# HRT.net
KiCad netlist of a schematic drawn in Altium Designer
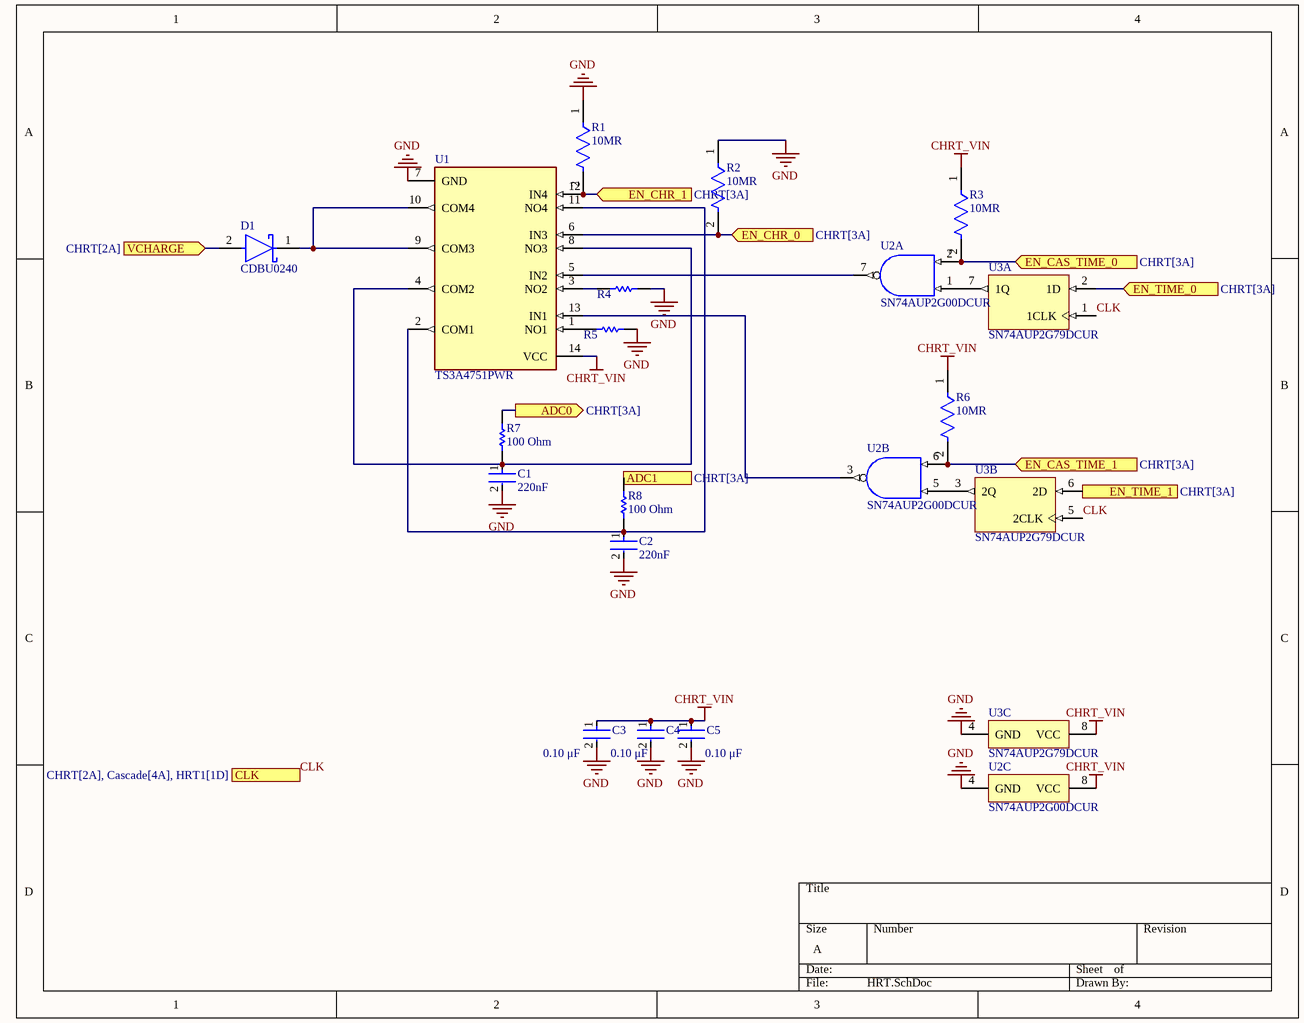
[diagram p0: HRT.SchDoc]

(export (version "E")
  (design (tool "Eeschema 10.0.6"))
  (components
    (comp (ref "C1")
      (value "GRM155R71C224KA12D")
      (footprint "FP-GRM155-0_05-IPC_C")
      (description "Chip Multilayer Ceramic Capacitors for General Purpose, 0402, 0.22uF, X7R, 15%, 10%, 16V")
      (fields
        (field (name "CAPACITANCE") "220nF")
        (field (name "VOLTAGE") "16V")
        (field (name "TOLERANCE") "10%")
      )
      (libsource (lib "Altium Content Vault") (part "02cd4be3c70576c341d710602a673aa"))
    )
    (comp (ref "C2")
      (value "GRM155R71C224KA12D")
      (footprint "FP-GRM155-0_05-IPC_C")
      (description "Chip Multilayer Ceramic Capacitors for General Purpose, 0402, 0.22uF, X7R, 15%, 10%, 16V")
      (fields
        (field (name "CAPACITANCE") "220nF")
        (field (name "VOLTAGE") "16V")
        (field (name "TOLERANCE") "10%")
      )
      (libsource (lib "Altium Content Vault") (part "02cd4be3c70576c341d710602a673aa"))
    )
    (comp (ref "C3")
      (value "C0402C104K8PACTU")
      (footprint "FP-C0402-BB-MFG")
      (description "CAP CER 0.1UF 10V X5R 0402")
      (fields
        (field (name "CAPACITANCE") "0.10 μF")
        (field (name "MANUFACTURER") "Kemet")
        (field (name "TOLERANCE") "0.1")
      )
      (libsource (lib "Altium Content Vault") (part "b4654b650e69147ec39a6b967a45e02"))
    )
    (comp (ref "C4")
      (value "C0402C104K8PACTU")
      (footprint "FP-C0402-BB-MFG")
      (description "CAP CER 0.1UF 10V X5R 0402")
      (fields
        (field (name "CAPACITANCE") "0.10 μF")
        (field (name "MANUFACTURER") "Kemet")
        (field (name "TOLERANCE") "0.1")
      )
      (libsource (lib "Altium Content Vault") (part "b4654b650e69147ec39a6b967a45e02"))
    )
    (comp (ref "C5")
      (value "C0402C104K8PACTU")
      (footprint "FP-C0402-BB-MFG")
      (description "CAP CER 0.1UF 10V X5R 0402")
      (fields
        (field (name "CAPACITANCE") "0.10 μF")
        (field (name "MANUFACTURER") "Kemet")
        (field (name "TOLERANCE") "0.1")
      )
      (libsource (lib "Altium Content Vault") (part "b4654b650e69147ec39a6b967a45e02"))
    )
    (comp (ref "D1")
      (value "CDBU0240")
      (footprint "FP-SOD-523F-MFG")
      (description "DIODE SCHOTTKY 40V 200MA 0603")
      (libsource (lib "Altium Content Vault") (part "1d6ec82d83fb6aee721767c19dac4b9"))
    )
    (comp (ref "R1")
      (value "CRCW040210M0JNED")
      (footprint "FP-CRCW0402-e3-IPC_C")
      (description "RES Thick Film, 10MΩ, 5%, 0.063W, 200ppm/°C, 0402")
      (fields (field (name "TOLERANCE") "5%") (field (name "RESISTANCE") "10MR"))
      (libsource (lib "Altium Content Vault") (part "1029c3af85768c4190bb7ad29bc67b5"))
    )
    (comp (ref "R2")
      (value "CRCW040210M0JNED")
      (footprint "FP-CRCW0402-e3-IPC_C")
      (description "RES Thick Film, 10MΩ, 5%, 0.063W, 200ppm/°C, 0402")
      (fields (field (name "TOLERANCE") "5%") (field (name "RESISTANCE") "10MR"))
      (libsource (lib "Altium Content Vault") (part "1029c3af85768c4190bb7ad29bc67b5"))
    )
    (comp (ref "R3")
      (value "CRCW040210M0JNED")
      (footprint "FP-CRCW0402-e3-IPC_C")
      (description "RES Thick Film, 10MΩ, 5%, 0.063W, 200ppm/°C, 0402")
      (fields (field (name "TOLERANCE") "5%") (field (name "RESISTANCE") "10MR"))
      (libsource (lib "Altium Content Vault") (part "1029c3af85768c4190bb7ad29bc67b5"))
    )
    (comp (ref "R4")
      (value "CRCW040222R0FKED")
      (footprint "RESC1005X40X25LL05T05")
      (fields (field (name "MANUFACTURER") "Vishay Dale"))
      (libsource (lib "Altium Content Vault") (part "RES"))
    )
    (comp (ref "R5")
      (value "CRCW040222R0FKED")
      (footprint "RESC1005X40X25LL05T05")
      (fields (field (name "MANUFACTURER") "Vishay Dale"))
      (libsource (lib "Altium Content Vault") (part "RES"))
    )
    (comp (ref "R6")
      (value "CRCW040210M0JNED")
      (footprint "FP-CRCW0402-e3-IPC_C")
      (description "RES Thick Film, 10MΩ, 5%, 0.063W, 200ppm/°C, 0402")
      (fields (field (name "TOLERANCE") "5%") (field (name "RESISTANCE") "10MR"))
      (libsource (lib "Altium Content Vault") (part "1029c3af85768c4190bb7ad29bc67b5"))
    )
    (comp (ref "R7")
      (value "ERJ-2RKF1000X")
      (footprint "RESC1005X40X25LL05T05")
      (description "Chip Resistor, 100 Ohm, +/- 1%, 100 mW, -55 to 155 degC, 0402 (1005 Metric), RoHS, Tape and Reel")
      (fields
        (field (name "MANUFACTURER") "Basic Passives")
        (field (name "TOLERANCE") "1%")
        (field (name "RESISTANCE") "100 Ohm")
      )
      (libsource (lib "Altium Content Vault") (part "RES-2"))
    )
    (comp (ref "R8")
      (value "ERJ-2RKF1000X")
      (footprint "RESC1005X40X25LL05T05")
      (description "Chip Resistor, 100 Ohm, +/- 1%, 100 mW, -55 to 155 degC, 0402 (1005 Metric), RoHS, Tape and Reel")
      (fields
        (field (name "MANUFACTURER") "Basic Passives")
        (field (name "TOLERANCE") "1%")
        (field (name "RESISTANCE") "100 Ohm")
      )
      (libsource (lib "Altium Content Vault") (part "RES-2"))
    )
    (comp (ref "U1")
      (value "TS3A4751PWR")
      (footprint "FP-PW0014A-IPC_C")
      (description "IC SWITCH QUAD SPST 14TSSOP")
      (libsource (lib "Altium Content Vault") (part "75fdcfb842d41a92b92a478e82e68ae"))
    )
    (comp (ref "U2")
      (value "SN74AUP2G00DCUR")
      (footprint "DCU0008A_L")
      (description "Low-Power Dual 2-Input Positive-NAND Gate, DCU0008A, LARGE T&R")
      (fields
        (field (name "GENERIC PART NUMBER") "SN74AUP2G00")
        (field (name "MANUFACTURER") "Texas Instruments")
      )
      (libsource (lib "Altium Content Vault") (part "TI-SN74XXX2GXXX-8"))
    )
    (comp (ref "U3")
      (value "SN74AUP2G79DCUR")
      (footprint "DCU0008A_L")
      (description "Low-Power Dual Positive-Edge-Triggered D-Type Flip-Flop, DCU0008A, LARGE T&R")
      (fields
        (field (name "MANUFACTURER") "Texas Instruments")
        (field (name "GENERIC PART NUMBER") "SN74AUP2G79")
      )
      (libsource (lib "Altium Content Vault") (part "TI-SN74XXX2G79-8_A"))
    )
  )
  (nets
    (net (code "1") (name "/ADC0") (class "Default")
      (node (ref "R7") (pin "2") (pinfunction "2_2") (pintype "passive"))
    )
    (net (code "2") (name "/ADC1") (class "Default")
      (node (ref "R8") (pin "2") (pinfunction "2_2") (pintype "passive"))
    )
    (net (code "3") (name "/CLK") (class "Default")
      (node (ref "U3") (pin "1") (pinfunction "1CLK_1") (pintype "input"))
      (node (ref "U3") (pin "5") (pinfunction "2CLK_5") (pintype "input"))
    )
    (net (code "4") (name "/EN_CAS_TIME_0") (class "Default")
      (node (ref "R3") (pin "2") (pinfunction "2_2") (pintype "passive"))
      (node (ref "U2") (pin "2") (pinfunction "1B_2") (pintype "input"))
    )
    (net (code "5") (name "/EN_CAS_TIME_1") (class "Default")
      (node (ref "R6") (pin "2") (pinfunction "2_2") (pintype "passive"))
      (node (ref "U2") (pin "6") (pinfunction "2B_6") (pintype "input"))
    )
    (net (code "6") (name "/EN_CHR_0") (class "Default")
      (node (ref "R2") (pin "2") (pinfunction "2_2") (pintype "passive"))
      (node (ref "U1") (pin "6") (pinfunction "IN3_6") (pintype "input"))
    )
    (net (code "7") (name "/EN_CHR_1") (class "Default")
      (node (ref "R1") (pin "2") (pinfunction "2_2") (pintype "passive"))
      (node (ref "U1") (pin "12") (pinfunction "IN4_12") (pintype "input"))
    )
    (net (code "8") (name "/EN_TIME_0") (class "Default")
      (node (ref "U3") (pin "2") (pinfunction "1D_2") (pintype "input"))
    )
    (net (code "9") (name "/EN_TIME_1") (class "Default")
      (node (ref "U3") (pin "6") (pinfunction "2D_6") (pintype "input"))
    )
    (net (code "10") (name "/VCHARGE") (class "Default")
      (node (ref "D1") (pin "2") (pinfunction "A_2") (pintype "passive"))
    )
    (net (code "11") (name "CHRT_VIN") (class "Default")
      (node (ref "C3") (pin "1") (pinfunction "1_1") (pintype "passive"))
      (node (ref "C4") (pin "1") (pinfunction "1_1") (pintype "passive"))
      (node (ref "C5") (pin "1") (pinfunction "1_1") (pintype "passive"))
      (node (ref "R3") (pin "1") (pinfunction "1_1") (pintype "passive"))
      (node (ref "R6") (pin "1") (pinfunction "1_1") (pintype "passive"))
      (node (ref "U1") (pin "14") (pinfunction "VCC_14") (pintype "power_in"))
      (node (ref "U2") (pin "8") (pinfunction "VCC_8") (pintype "power_in"))
      (node (ref "U3") (pin "8") (pinfunction "VCC_8") (pintype "power_in"))
    )
    (net (code "12") (name "GND") (class "Default")
      (node (ref "C1") (pin "2") (pinfunction "2_2") (pintype "passive"))
      (node (ref "C2") (pin "2") (pinfunction "2_2") (pintype "passive"))
      (node (ref "C3") (pin "2") (pinfunction "2_2") (pintype "passive"))
      (node (ref "C4") (pin "2") (pinfunction "2_2") (pintype "passive"))
      (node (ref "C5") (pin "2") (pinfunction "2_2") (pintype "passive"))
      (node (ref "R1") (pin "1") (pinfunction "1_1") (pintype "passive"))
      (node (ref "R2") (pin "1") (pinfunction "1_1") (pintype "passive"))
      (node (ref "R4") (pin "2") (pinfunction "2_2") (pintype "passive"))
      (node (ref "R5") (pin "2") (pinfunction "2_2") (pintype "passive"))
      (node (ref "U1") (pin "7") (pinfunction "GND_7") (pintype "power_in"))
      (node (ref "U2") (pin "4") (pinfunction "GND_4") (pintype "power_in"))
      (node (ref "U3") (pin "4") (pinfunction "GND_4") (pintype "power_in"))
    )
    (net (code "13") (name "Net-(D1-C)") (class "Default")
      (node (ref "D1") (pin "1") (pinfunction "C_1") (pintype "passive"))
      (node (ref "U1") (pin "10") (pinfunction "COM4_10") (pintype "output"))
      (node (ref "U1") (pin "9") (pinfunction "COM3_9") (pintype "output"))
    )
    (net (code "14") (name "Net-(U1-COM1)") (class "Default")
      (node (ref "C2") (pin "1") (pinfunction "1_1") (pintype "passive"))
      (node (ref "R8") (pin "1") (pinfunction "1_1") (pintype "passive"))
      (node (ref "U1") (pin "11") (pinfunction "NO4_11") (pintype "input"))
      (node (ref "U1") (pin "2") (pinfunction "COM1_2") (pintype "output"))
    )
    (net (code "15") (name "Net-(U1-COM2)") (class "Default")
      (node (ref "C1") (pin "1") (pinfunction "1_1") (pintype "passive"))
      (node (ref "R7") (pin "1") (pinfunction "1_1") (pintype "passive"))
      (node (ref "U1") (pin "4") (pinfunction "COM2_4") (pintype "output"))
      (node (ref "U1") (pin "8") (pinfunction "NO3_8") (pintype "input"))
    )
    (net (code "16") (name "Net-(U1-IN1)") (class "Default")
      (node (ref "U1") (pin "13") (pinfunction "IN1_13") (pintype "input"))
      (node (ref "U2") (pin "3") (pinfunction "2Y_3") (pintype "output"))
    )
    (net (code "17") (name "Net-(U1-IN2)") (class "Default")
      (node (ref "U1") (pin "5") (pinfunction "IN2_5") (pintype "input"))
      (node (ref "U2") (pin "7") (pinfunction "1Y_7") (pintype "output"))
    )
    (net (code "18") (name "Net-(U1-NO1)") (class "Default")
      (node (ref "R5") (pin "1") (pinfunction "1_1") (pintype "passive"))
      (node (ref "U1") (pin "1") (pinfunction "NO1_1") (pintype "input"))
    )
    (net (code "19") (name "Net-(U1-NO2)") (class "Default")
      (node (ref "R4") (pin "1") (pinfunction "1_1") (pintype "passive"))
      (node (ref "U1") (pin "3") (pinfunction "NO2_3") (pintype "input"))
    )
    (net (code "20") (name "Net-(U2A-1A)") (class "Default")
      (node (ref "U2") (pin "1") (pinfunction "1A_1") (pintype "input"))
      (node (ref "U3") (pin "7") (pinfunction "1Q_7") (pintype "output"))
    )
    (net (code "21") (name "Net-(U2B-2A)") (class "Default")
      (node (ref "U2") (pin "5") (pinfunction "2A_5") (pintype "input"))
      (node (ref "U3") (pin "3") (pinfunction "2Q_3") (pintype "output"))
    )
  )
)
